# Half-Bridge.net
KiCad netlist of a schematic drawn in Altium Designer
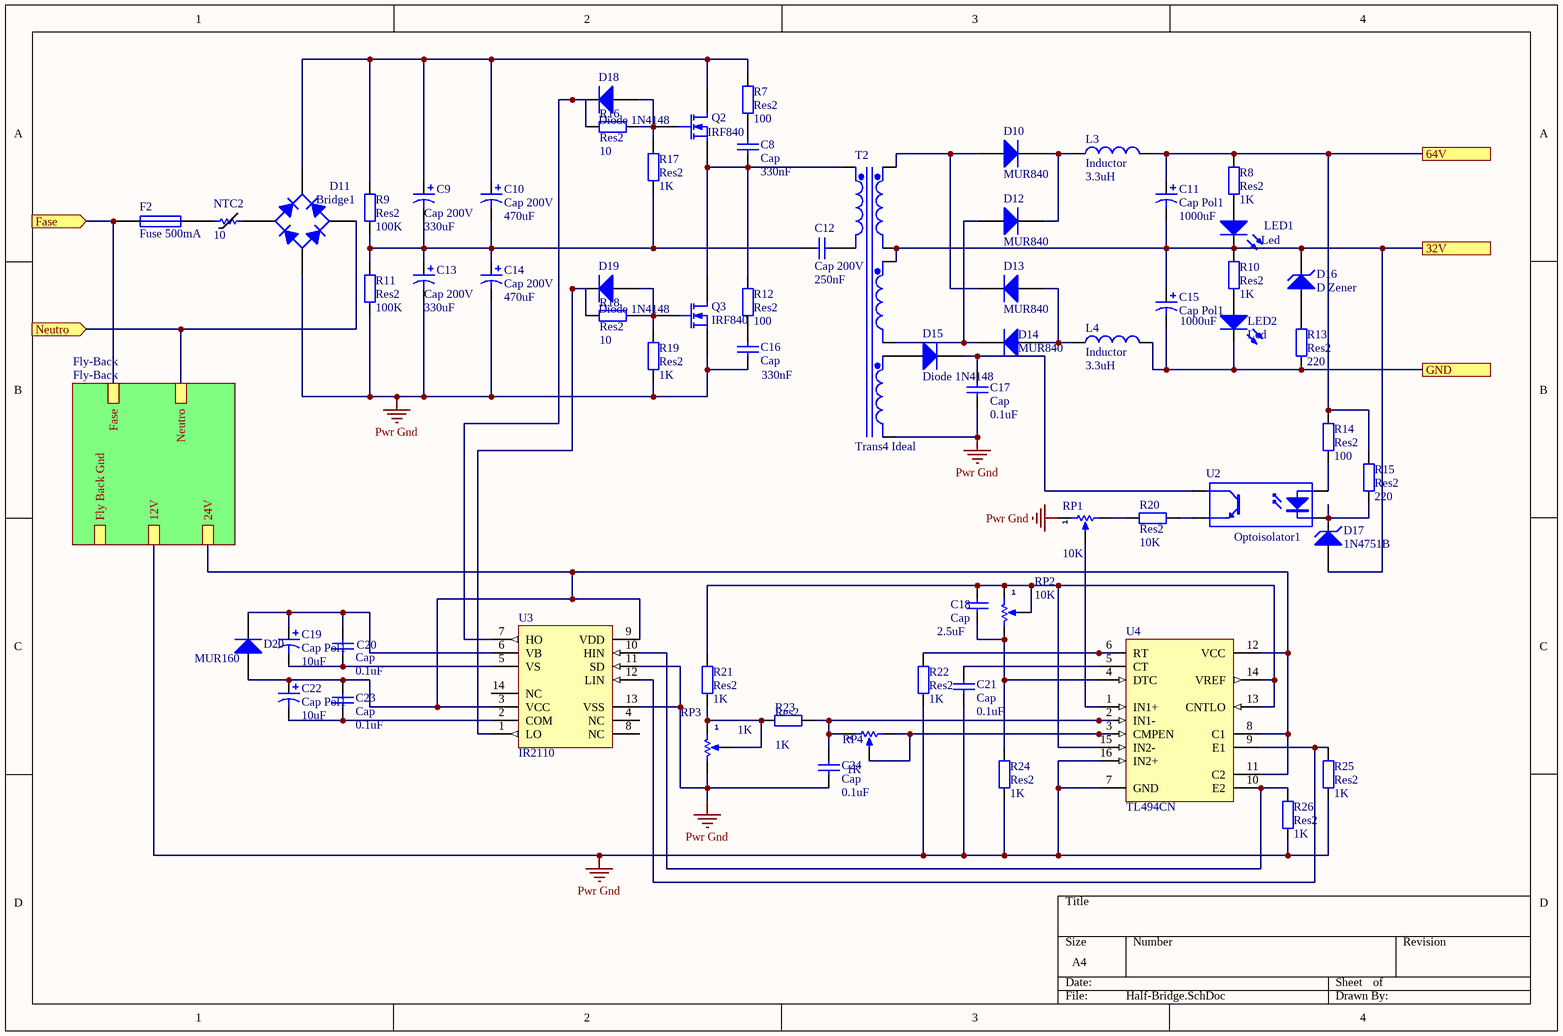
[diagram p0: Half-Bridge.SchDoc]

(export (version "E")
  (design (tool "Eeschema 10.0.6"))
  (components
    (comp (ref "C8")
      (value "Cap")
      (footprint "RAD-0.3")
      (description "Capacitor")
      (fields (field (name "ALTIUM_VALUE") "330nF") (field (name "PUBLISHER") "Altium Limited"))
      (libsource (lib "Miscellaneous Devices") (part "Cap"))
    )
    (comp (ref "C9")
      (value "Cap 200V")
      (footprint "RB7.6-15")
      (description "Polarized Capacitor (Radial)")
      (fields (field (name "ALTIUM_VALUE") "330uF") (field (name "PUBLISHER") "Altium Limited"))
      (libsource (lib "Miscellaneous Devices") (part "Cap Pol1"))
    )
    (comp (ref "C10")
      (value "Cap 200V")
      (footprint "RB7.6-15")
      (description "Polarized Capacitor (Radial)")
      (fields (field (name "ALTIUM_VALUE") "470uF") (field (name "PUBLISHER") "Altium Limited"))
      (libsource (lib "Miscellaneous Devices") (part "Cap Pol1"))
    )
    (comp (ref "C11")
      (value "Cap Pol1")
      (footprint "RB7.6-15")
      (description "Polarized Capacitor (Radial)")
      (fields (field (name "ALTIUM_VALUE") "1000uF") (field (name "PUBLISHER") "Altium Limited"))
      (libsource (lib "Miscellaneous Devices") (part "Cap Pol1"))
    )
    (comp (ref "C12")
      (value "Cap 200V")
      (footprint "RAD-0.3")
      (description "Capacitor")
      (fields (field (name "ALTIUM_VALUE") "250nF") (field (name "PUBLISHER") "Altium Limited"))
      (libsource (lib "Miscellaneous Devices") (part "Cap"))
    )
    (comp (ref "C13")
      (value "Cap 200V")
      (footprint "RB7.6-15")
      (description "Polarized Capacitor (Radial)")
      (fields (field (name "ALTIUM_VALUE") "330uF") (field (name "PUBLISHER") "Altium Limited"))
      (libsource (lib "Miscellaneous Devices") (part "Cap Pol1"))
    )
    (comp (ref "C14")
      (value "Cap 200V")
      (footprint "RB7.6-15")
      (description "Polarized Capacitor (Radial)")
      (fields (field (name "ALTIUM_VALUE") "470uF") (field (name "PUBLISHER") "Altium Limited"))
      (libsource (lib "Miscellaneous Devices") (part "Cap Pol1"))
    )
    (comp (ref "C15")
      (value "Cap Pol1")
      (footprint "RB7.6-15")
      (description "Polarized Capacitor (Radial)")
      (fields (field (name "ALTIUM_VALUE") "1000uF") (field (name "PUBLISHER") "Altium Limited"))
      (libsource (lib "Miscellaneous Devices") (part "Cap Pol1"))
    )
    (comp (ref "C16")
      (value "Cap")
      (footprint "RAD-0.3")
      (description "Capacitor")
      (fields (field (name "ALTIUM_VALUE") "330nF") (field (name "PUBLISHER") "Altium Limited"))
      (libsource (lib "Miscellaneous Devices") (part "Cap"))
    )
    (comp (ref "C17")
      (value "Cap")
      (footprint "RAD-0.3")
      (description "Capacitor")
      (fields (field (name "ALTIUM_VALUE") "0.1uF") (field (name "PUBLISHER") "Altium Limited"))
      (libsource (lib "Miscellaneous Devices") (part "Cap"))
    )
    (comp (ref "C18")
      (value "Cap")
      (footprint "RAD-0.3")
      (description "Capacitor")
      (fields (field (name "ALTIUM_VALUE") "2.5uF") (field (name "PUBLISHER") "Altium Limited"))
      (libsource (lib "Miscellaneous Devices") (part "Cap"))
    )
    (comp (ref "C19")
      (value "Cap Pol1")
      (footprint "RB7.6-15")
      (description "Polarized Capacitor (Radial)")
      (fields (field (name "ALTIUM_VALUE") "10uF") (field (name "PUBLISHER") "Altium Limited"))
      (libsource (lib "Miscellaneous Devices") (part "Cap Pol1"))
    )
    (comp (ref "C20")
      (value "Cap")
      (footprint "RAD-0.3")
      (description "Capacitor")
      (fields (field (name "ALTIUM_VALUE") "0.1uF") (field (name "PUBLISHER") "Altium Limited"))
      (libsource (lib "Miscellaneous Devices") (part "Cap"))
    )
    (comp (ref "C21")
      (value "Cap")
      (footprint "RAD-0.3")
      (description "Capacitor")
      (fields (field (name "ALTIUM_VALUE") "0.1uF") (field (name "PUBLISHER") "Altium Limited"))
      (libsource (lib "Miscellaneous Devices") (part "Cap"))
    )
    (comp (ref "C22")
      (value "Cap Pol1")
      (footprint "RB7.6-15")
      (description "Polarized Capacitor (Radial)")
      (fields (field (name "ALTIUM_VALUE") "10uF") (field (name "PUBLISHER") "Altium Limited"))
      (libsource (lib "Miscellaneous Devices") (part "Cap Pol1"))
    )
    (comp (ref "C23")
      (value "Cap")
      (footprint "RAD-0.3")
      (description "Capacitor")
      (fields (field (name "ALTIUM_VALUE") "0.1uF") (field (name "PUBLISHER") "Altium Limited"))
      (libsource (lib "Miscellaneous Devices") (part "Cap"))
    )
    (comp (ref "C24")
      (value "Cap")
      (footprint "RAD-0.3")
      (description "Capacitor")
      (fields (field (name "ALTIUM_VALUE") "0.1uF") (field (name "PUBLISHER") "Altium Limited"))
      (libsource (lib "Miscellaneous Devices") (part "Cap"))
    )
    (comp (ref "D10")
      (value "MUR840")
      (footprint "DO-35")
      (description "High Conductance Fast Diode")
      (fields (field (name "PUBLISHER") "Altium Limited"))
      (libsource (lib "Miscellaneous Devices") (part "Diode 1N4148"))
    )
    (comp (ref "D11")
      (value "Bridge1")
      (footprint "D-38")
      (description "Full Wave Diode Bridge")
      (fields (field (name "PUBLISHER") "Altium Limited"))
      (libsource (lib "Miscellaneous Devices") (part "Bridge1"))
    )
    (comp (ref "D12")
      (value "MUR840")
      (footprint "DO-35")
      (description "High Conductance Fast Diode")
      (fields (field (name "PUBLISHER") "Altium Limited"))
      (libsource (lib "Miscellaneous Devices") (part "Diode 1N4148"))
    )
    (comp (ref "D13")
      (value "MUR840")
      (footprint "DO-35")
      (description "High Conductance Fast Diode")
      (fields (field (name "PUBLISHER") "Altium Limited"))
      (libsource (lib "Miscellaneous Devices") (part "Diode 1N4148"))
    )
    (comp (ref "D14")
      (value "MUR840")
      (footprint "DO-35")
      (description "High Conductance Fast Diode")
      (fields (field (name "PUBLISHER") "Altium Limited"))
      (libsource (lib "Miscellaneous Devices") (part "Diode 1N4148"))
    )
    (comp (ref "D15")
      (value "Diode 1N4148")
      (footprint "DO-35")
      (description "High Conductance Fast Diode")
      (fields (field (name "PUBLISHER") "Altium Limited"))
      (libsource (lib "Miscellaneous Devices") (part "Diode 1N4148"))
    )
    (comp (ref "D16")
      (value "D Zener")
      (footprint "DIODE-0.7")
      (description "Zener Diode")
      (fields (field (name "PUBLISHER") "Altium Limited"))
      (libsource (lib "Miscellaneous Devices") (part "D Zener"))
    )
    (comp (ref "D17")
      (value "1N4751B")
      (footprint "DIODE-0.7")
      (description "Zener Diode")
      (fields (field (name "PUBLISHER") "Altium Limited"))
      (libsource (lib "Miscellaneous Devices") (part "D Zener"))
    )
    (comp (ref "D18")
      (value "Diode 1N4148")
      (footprint "DO-35")
      (description "High Conductance Fast Diode")
      (fields (field (name "PUBLISHER") "Altium Limited"))
      (libsource (lib "Miscellaneous Devices") (part "Diode 1N4148"))
    )
    (comp (ref "D19")
      (value "Diode 1N4148")
      (footprint "DO-35")
      (description "High Conductance Fast Diode")
      (fields (field (name "PUBLISHER") "Altium Limited"))
      (libsource (lib "Miscellaneous Devices") (part "Diode 1N4148"))
    )
    (comp (ref "D20")
      (value "MUR160")
      (footprint "DO-35")
      (description "High Conductance Fast Diode")
      (fields (field (name "PUBLISHER") "Altium Limited"))
      (libsource (lib "Miscellaneous Devices") (part "Diode 1N4148"))
    )
    (comp (ref "F2")
      (value "Fuse 500mA")
      (footprint "PIN-W2/E2.8")
      (description "Fuse")
      (fields (field (name "PUBLISHER") "Altium Limited"))
      (libsource (lib "Miscellaneous Devices") (part "Fuse 1"))
    )
    (comp (ref "L3")
      (value "Inductor")
      (footprint "0402-A")
      (fields (field (name "ALTIUM_VALUE") "3.3uH") (field (name "PUBLISHER") "Altium Limited"))
      (libsource (lib "Miscellaneous Devices") (part "Inductor"))
    )
    (comp (ref "L4")
      (value "Inductor")
      (footprint "0402-A")
      (fields (field (name "ALTIUM_VALUE") "3.3uH") (field (name "PUBLISHER") "Altium Limited"))
      (libsource (lib "Miscellaneous Devices") (part "Inductor"))
    )
    (comp (ref "LED1")
      (value "Diodo Led")
      (footprint "Led 3mm AMARILLO")
      (description "Led 3mm")
      (fields (field (name "VALOR") "Led"))
      (libsource (lib "RUF-Dispositivos-Grales") (part "Diodo Led"))
    )
    (comp (ref "LED2")
      (value "Diodo Led")
      (footprint "Led 3mm AMARILLO")
      (description "Led 3mm")
      (fields (field (name "VALOR") "Led"))
      (libsource (lib "RUF-Dispositivos-Grales") (part "Diodo Led"))
    )
    (comp (ref "NTC2")
      (value "Termistor NTC")
      (footprint "R0805")
      (description "Termistor NTC SMD")
      (fields (field (name "VALOR") "10"))
      (libsource (lib "RUF-Dispositivos-Grales") (part "Termistor NTC"))
    )
    (comp (ref "Q2")
      (value "IRF840")
      (footprint "E3")
      (description "N-Channel MOSFET")
      (fields (field (name "PUBLISHER") "Altium Limited"))
      (libsource (lib "Miscellaneous Devices") (part "MOSFET-N"))
    )
    (comp (ref "Q3")
      (value "IRF840")
      (footprint "E3")
      (description "N-Channel MOSFET")
      (fields (field (name "PUBLISHER") "Altium Limited"))
      (libsource (lib "Miscellaneous Devices") (part "MOSFET-N"))
    )
    (comp (ref "R7")
      (value "Res2")
      (footprint "AXIAL-0.4")
      (description "Resistor")
      (fields (field (name "ALTIUM_VALUE") "100") (field (name "PUBLISHER") "Altium Limited"))
      (libsource (lib "") (part "Res2_1"))
    )
    (comp (ref "R8")
      (value "Res2")
      (footprint "AXIAL-0.4")
      (description "Resistor")
      (fields (field (name "ALTIUM_VALUE") "1K") (field (name "PUBLISHER") "Altium Limited"))
      (libsource (lib "") (part "Res2_1"))
    )
    (comp (ref "R9")
      (value "Res2")
      (footprint "AXIAL-0.4")
      (description "Resistor")
      (fields (field (name "ALTIUM_VALUE") "100K") (field (name "PUBLISHER") "Altium Limited"))
      (libsource (lib "") (part "Res2_1"))
    )
    (comp (ref "R10")
      (value "Res2")
      (footprint "AXIAL-0.4")
      (description "Resistor")
      (fields (field (name "ALTIUM_VALUE") "1K") (field (name "PUBLISHER") "Altium Limited"))
      (libsource (lib "") (part "Res2_1"))
    )
    (comp (ref "R11")
      (value "Res2")
      (footprint "AXIAL-0.4")
      (description "Resistor")
      (fields (field (name "ALTIUM_VALUE") "100K") (field (name "PUBLISHER") "Altium Limited"))
      (libsource (lib "") (part "Res2_1"))
    )
    (comp (ref "R12")
      (value "Res2")
      (footprint "AXIAL-0.4")
      (description "Resistor")
      (fields (field (name "ALTIUM_VALUE") "100") (field (name "PUBLISHER") "Altium Limited"))
      (libsource (lib "") (part "Res2_1"))
    )
    (comp (ref "R13")
      (value "Res2")
      (footprint "AXIAL-0.4")
      (description "Resistor")
      (fields (field (name "ALTIUM_VALUE") "220") (field (name "PUBLISHER") "Altium Limited"))
      (libsource (lib "") (part "Res2_1"))
    )
    (comp (ref "R14")
      (value "Res2")
      (footprint "AXIAL-0.4")
      (description "Resistor")
      (fields (field (name "ALTIUM_VALUE") "100") (field (name "PUBLISHER") "Altium Limited"))
      (libsource (lib "") (part "Res2_1"))
    )
    (comp (ref "R15")
      (value "Res2")
      (footprint "AXIAL-0.4")
      (description "Resistor")
      (fields (field (name "ALTIUM_VALUE") "220") (field (name "PUBLISHER") "Altium Limited"))
      (libsource (lib "") (part "Res2_1"))
    )
    (comp (ref "R16")
      (value "Res2")
      (footprint "AXIAL-0.4")
      (description "Resistor")
      (fields (field (name "ALTIUM_VALUE") "10") (field (name "PUBLISHER") "Altium Limited"))
      (libsource (lib "") (part "Res2_3"))
    )
    (comp (ref "R17")
      (value "Res2")
      (footprint "AXIAL-0.4")
      (description "Resistor")
      (fields (field (name "ALTIUM_VALUE") "1K") (field (name "PUBLISHER") "Altium Limited"))
      (libsource (lib "") (part "Res2_1"))
    )
    (comp (ref "R18")
      (value "Res2")
      (footprint "AXIAL-0.4")
      (description "Resistor")
      (fields (field (name "ALTIUM_VALUE") "10") (field (name "PUBLISHER") "Altium Limited"))
      (libsource (lib "") (part "Res2_2"))
    )
    (comp (ref "R19")
      (value "Res2")
      (footprint "AXIAL-0.4")
      (description "Resistor")
      (fields (field (name "ALTIUM_VALUE") "1K") (field (name "PUBLISHER") "Altium Limited"))
      (libsource (lib "Miscellaneous Devices") (part "Res2"))
    )
    (comp (ref "R20")
      (value "Res2")
      (footprint "AXIAL-0.4")
      (description "Resistor")
      (fields (field (name "ALTIUM_VALUE") "10K") (field (name "PUBLISHER") "Altium Limited"))
      (libsource (lib "") (part "Res2_2"))
    )
    (comp (ref "R21")
      (value "Res2")
      (footprint "AXIAL-0.4")
      (description "Resistor")
      (fields (field (name "ALTIUM_VALUE") "1K") (field (name "PUBLISHER") "Altium Limited"))
      (libsource (lib "") (part "Res2_1"))
    )
    (comp (ref "R22")
      (value "Res2")
      (footprint "AXIAL-0.4")
      (description "Resistor")
      (fields (field (name "ALTIUM_VALUE") "1K") (field (name "PUBLISHER") "Altium Limited"))
      (libsource (lib "") (part "Res2_1"))
    )
    (comp (ref "R23")
      (value "Res2")
      (footprint "AXIAL-0.4")
      (description "Resistor")
      (fields (field (name "ALTIUM_VALUE") "1K") (field (name "PUBLISHER") "Altium Limited"))
      (libsource (lib "") (part "Res2_3"))
    )
    (comp (ref "R24")
      (value "Res2")
      (footprint "AXIAL-0.4")
      (description "Resistor")
      (fields (field (name "ALTIUM_VALUE") "1K") (field (name "PUBLISHER") "Altium Limited"))
      (libsource (lib "") (part "Res2_1"))
    )
    (comp (ref "R25")
      (value "Res2")
      (footprint "AXIAL-0.4")
      (description "Resistor")
      (fields (field (name "ALTIUM_VALUE") "1K") (field (name "PUBLISHER") "Altium Limited"))
      (libsource (lib "") (part "Res2_1"))
    )
    (comp (ref "R26")
      (value "Res2")
      (footprint "AXIAL-0.4")
      (description "Resistor")
      (fields (field (name "ALTIUM_VALUE") "1K") (field (name "PUBLISHER") "Altium Limited"))
      (libsource (lib "") (part "Res2_1"))
    )
    (comp (ref "RP1")
      (value "Trimpot")
      (footprint "Trimpot Multivuelta Horizontal")
      (description "Preset")
      (fields (field (name "VALOR") "10K"))
      (libsource (lib "RUF-Dispositivos-Grales") (part "Trimpot"))
    )
    (comp (ref "RP2")
      (value "Trimpot")
      (footprint "Trimpot Multivuelta Horizontal")
      (description "Preset")
      (fields (field (name "VALOR") "10K"))
      (libsource (lib "RUF-Dispositivos-Grales") (part "Trimpot"))
    )
    (comp (ref "RP3")
      (value "Trimpot")
      (footprint "Trimpot Multivuelta Horizontal")
      (description "Preset")
      (fields (field (name "VALOR") "1K"))
      (libsource (lib "RUF-Dispositivos-Grales") (part "Trimpot"))
    )
    (comp (ref "RP4")
      (value "Trimpot")
      (footprint "Trimpot Multivuelta Horizontal")
      (description "Preset")
      (fields (field (name "VALOR") "1K"))
      (libsource (lib "RUF-Dispositivos-Grales") (part "Trimpot"))
    )
    (comp (ref "T2")
      (value "Trans4 Ideal")
      (footprint "TRF_8")
      (description "Four-winding Transformer (Ideal)")
      (fields (field (name "PUBLISHER") "Altium Limited"))
      (libsource (lib "Miscellaneous Devices") (part "Trans4 Ideal"))
    )
    (comp (ref "U2")
      (value "Optoisolator1")
      (footprint "DIP-4")
      (description "4-Pin Phototransistor Optocoupler")
      (fields (field (name "PUBLISHER") "Altium Limited"))
      (libsource (lib "Miscellaneous Devices") (part "Optoisolator1"))
    )
    (comp (ref "U3")
      (value "IR2110")
      (footprint "PDIP14")
      (description "High and Low Side Driver")
      (fields (field (name "PUBLISHER") "Altium Limited"))
      (libsource (lib "IR Interface Bridge Driver") (part "IR2110"))
    )
    (comp (ref "U4")
      (value "TL494CN")
      (footprint "DIP-16")
      (description "Switchmode Pulse Width Modulation Control Circuit")
      (fields (field (name "PUBLISHER") "Altium Limited"))
      (libsource (lib "ON Semi Power Mgt SMPS Controller") (part "TL494CN"))
    )
  )
  (nets
    (net (code "1") (name "/24V") (class "Default")
      (node (ref "C22") (pin "1") (pinfunction "1_1") (pintype "passive"))
      (node (ref "C23") (pin "2") (pinfunction "2_2") (pintype "passive"))
      (node (ref "D20") (pin "1") (pinfunction "A_1") (pintype "passive"))
      (node (ref "U3") (pin "3") (pinfunction "VCC_3") (pintype "power_in"))
      (node (ref "U3") (pin "9") (pinfunction "VDD_9") (pintype "power_in"))
      (node (ref "U4") (pin "11") (pinfunction "C2_11") (pintype "passive"))
      (node (ref "U4") (pin "12") (pinfunction "VCC_12") (pintype "power_in"))
      (node (ref "U4") (pin "8") (pinfunction "C1_8") (pintype "passive"))
    )
    (net (code "2") (name "/32V") (class "Default")
      (node (ref "C11") (pin "2") (pinfunction "2_2") (pintype "passive"))
      (node (ref "C15") (pin "1") (pinfunction "1_1") (pintype "passive"))
      (node (ref "D16") (pin "2") (pinfunction "K_2") (pintype "passive"))
      (node (ref "D17") (pin "1") (pinfunction "A_1") (pintype "passive"))
      (node (ref "LED1") (pin "2") (pinfunction "K_2") (pintype "passive"))
      (node (ref "R10") (pin "2") (pinfunction "2_2") (pintype "passive"))
      (node (ref "T2") (pin "4") (pinfunction "Sec1-_4") (pintype "passive"))
      (node (ref "T2") (pin "5") (pinfunction "Sec2+_5") (pintype "passive"))
    )
    (net (code "3") (name "/64V") (class "Default")
      (node (ref "C11") (pin "1") (pinfunction "1_1") (pintype "passive"))
      (node (ref "L3") (pin "2") (pinfunction "2_2") (pintype "passive"))
      (node (ref "R14") (pin "2") (pinfunction "2_2") (pintype "passive"))
      (node (ref "R15") (pin "2") (pinfunction "2_2") (pintype "passive"))
      (node (ref "R8") (pin "2") (pinfunction "2_2") (pintype "passive"))
    )
    (net (code "4") (name "/Fase") (class "Default")
      (node (ref "F2") (pin "1") (pinfunction "1_1") (pintype "passive"))
    )
    (net (code "6") (name "/GND") (class "Default")
      (node (ref "C15") (pin "2") (pinfunction "2_2") (pintype "passive"))
      (node (ref "L4") (pin "2") (pinfunction "2_2") (pintype "passive"))
      (node (ref "LED2") (pin "2") (pinfunction "K_2") (pintype "passive"))
      (node (ref "R13") (pin "1") (pinfunction "1_1") (pintype "passive"))
    )
    (net (code "7") (name "/Neutro") (class "Default")
      (node (ref "D11") (pin "2") (pinfunction "C_2") (pintype "passive"))
    )
    (net (code "8") (name "Net-(C8-Pad2)") (class "Default")
      (node (ref "C8") (pin "2") (pinfunction "2_2") (pintype "passive"))
      (node (ref "R7") (pin "1") (pinfunction "1_1") (pintype "passive"))
    )
    (net (code "9") (name "Net-(C10-Pad2)") (class "Default")
      (node (ref "C10") (pin "2") (pinfunction "2_2") (pintype "passive"))
      (node (ref "C12") (pin "1") (pinfunction "1_1") (pintype "passive"))
      (node (ref "C13") (pin "1") (pinfunction "1_1") (pintype "passive"))
      (node (ref "C14") (pin "1") (pinfunction "1_1") (pintype "passive"))
      (node (ref "C9") (pin "2") (pinfunction "2_2") (pintype "passive"))
      (node (ref "R11") (pin "2") (pinfunction "2_2") (pintype "passive"))
      (node (ref "R17") (pin "1") (pinfunction "1_1") (pintype "passive"))
      (node (ref "R9") (pin "1") (pinfunction "1_1") (pintype "passive"))
    )
    (net (code "10") (name "Net-(C16-Pad2)") (class "Default")
      (node (ref "C16") (pin "2") (pinfunction "2_2") (pintype "passive"))
      (node (ref "R12") (pin "1") (pinfunction "1_1") (pintype "passive"))
    )
    (net (code "11") (name "Net-(D10-A)") (class "Default")
      (node (ref "D10") (pin "1") (pinfunction "A_1") (pintype "passive"))
      (node (ref "D13") (pin "2") (pinfunction "K_2") (pintype "passive"))
      (node (ref "T2") (pin "3") (pinfunction "Sec1+_3") (pintype "passive"))
    )
    (net (code "12") (name "Net-(D10-K)") (class "Default")
      (node (ref "D10") (pin "2") (pinfunction "K_2") (pintype "passive"))
      (node (ref "D12") (pin "2") (pinfunction "K_2") (pintype "passive"))
      (node (ref "L3") (pin "1") (pinfunction "1_1") (pintype "passive"))
    )
    (net (code "13") (name "Net-(D11-C-Pad4)") (class "Default")
      (node (ref "D11") (pin "4") (pinfunction "C_4") (pintype "passive"))
      (node (ref "NTC2") (pin "1") (pinfunction "1_1") (pintype "passive"))
    )
    (net (code "14") (name "Net-(D11-K)") (class "Default")
      (node (ref "C10") (pin "1") (pinfunction "1_1") (pintype "passive"))
      (node (ref "C9") (pin "1") (pinfunction "1_1") (pintype "passive"))
      (node (ref "D11") (pin "1") (pinfunction "K_1") (pintype "passive"))
      (node (ref "Q2") (pin "1") (pinfunction "D_1") (pintype "passive"))
      (node (ref "R7") (pin "2") (pinfunction "2_2") (pintype "passive"))
      (node (ref "R9") (pin "2") (pinfunction "2_2") (pintype "passive"))
    )
    (net (code "15") (name "Net-(D12-A)") (class "Default")
      (node (ref "D12") (pin "1") (pinfunction "A_1") (pintype "passive"))
      (node (ref "D14") (pin "2") (pinfunction "K_2") (pintype "passive"))
      (node (ref "T2") (pin "6") (pinfunction "Sec2-_6") (pintype "passive"))
    )
    (net (code "16") (name "Net-(D13-A)") (class "Default")
      (node (ref "D13") (pin "1") (pinfunction "A_1") (pintype "passive"))
      (node (ref "D14") (pin "1") (pinfunction "A_1") (pintype "passive"))
      (node (ref "L4") (pin "1") (pinfunction "1_1") (pintype "passive"))
    )
    (net (code "17") (name "Net-(D15-A)") (class "Default")
      (node (ref "D15") (pin "1") (pinfunction "A_1") (pintype "passive"))
      (node (ref "T2") (pin "7") (pinfunction "Sec3+_7") (pintype "passive"))
    )
    (net (code "18") (name "Net-(D15-K)") (class "Default")
      (node (ref "C17") (pin "2") (pinfunction "2_2") (pintype "passive"))
      (node (ref "D15") (pin "2") (pinfunction "K_2") (pintype "passive"))
      (node (ref "U2") (pin "4") (pinfunction "C_4") (pintype "passive"))
    )
    (net (code "19") (name "Net-(D16-A)") (class "Default")
      (node (ref "D16") (pin "1") (pinfunction "A_1") (pintype "passive"))
      (node (ref "R13") (pin "2") (pinfunction "2_2") (pintype "passive"))
    )
    (net (code "20") (name "Net-(D17-K)") (class "Default")
      (node (ref "D17") (pin "2") (pinfunction "K_2") (pintype "passive"))
      (node (ref "R15") (pin "1") (pinfunction "1_1") (pintype "passive"))
      (node (ref "U2") (pin "2") (pinfunction "K_2") (pintype "passive"))
    )
    (net (code "21") (name "Net-(D18-A)") (class "Default")
      (node (ref "D18") (pin "1") (pinfunction "A_1") (pintype "passive"))
      (node (ref "Q2") (pin "2") (pinfunction "G_2") (pintype "passive"))
      (node (ref "R16") (pin "2") (pinfunction "2_2") (pintype "passive"))
      (node (ref "R17") (pin "2") (pinfunction "2_2") (pintype "passive"))
    )
    (net (code "22") (name "Net-(D18-K)") (class "Default")
      (node (ref "D18") (pin "2") (pinfunction "K_2") (pintype "passive"))
      (node (ref "R16") (pin "1") (pinfunction "1_1") (pintype "passive"))
      (node (ref "U3") (pin "7") (pinfunction "HO_7") (pintype "output"))
    )
    (net (code "23") (name "Net-(D19-A)") (class "Default")
      (node (ref "D19") (pin "1") (pinfunction "A_1") (pintype "passive"))
      (node (ref "Q3") (pin "2") (pinfunction "G_2") (pintype "passive"))
      (node (ref "R18") (pin "1") (pinfunction "1_1") (pintype "passive"))
      (node (ref "R19") (pin "1") (pinfunction "1_1") (pintype "passive"))
    )
    (net (code "24") (name "Net-(D19-K)") (class "Default")
      (node (ref "D19") (pin "2") (pinfunction "K_2") (pintype "passive"))
      (node (ref "R18") (pin "2") (pinfunction "2_2") (pintype "passive"))
      (node (ref "U3") (pin "1") (pinfunction "LO_1") (pintype "output"))
    )
    (net (code "25") (name "Net-(D20-K)") (class "Default")
      (node (ref "C19") (pin "1") (pinfunction "1_1") (pintype "passive"))
      (node (ref "C20") (pin "2") (pinfunction "2_2") (pintype "passive"))
      (node (ref "D20") (pin "2") (pinfunction "K_2") (pintype "passive"))
      (node (ref "U3") (pin "6") (pinfunction "VB_6") (pintype "power_in"))
    )
    (net (code "26") (name "Net-(F2-Pad2)") (class "Default")
      (node (ref "F2") (pin "2") (pinfunction "2_2") (pintype "passive"))
      (node (ref "NTC2") (pin "2") (pinfunction "2_2") (pintype "passive"))
    )
    (net (code "27") (name "Net-(LED1-A)") (class "Default")
      (node (ref "LED1") (pin "1") (pinfunction "A_1") (pintype "passive"))
      (node (ref "R8") (pin "1") (pinfunction "1_1") (pintype "passive"))
    )
    (net (code "28") (name "Net-(LED2-A)") (class "Default")
      (node (ref "LED2") (pin "1") (pinfunction "A_1") (pintype "passive"))
      (node (ref "R10") (pin "1") (pinfunction "1_1") (pintype "passive"))
    )
    (net (code "29") (name "Net-(Q2-S)") (class "Default")
      (node (ref "C8") (pin "1") (pinfunction "1_1") (pintype "passive"))
      (node (ref "Q2") (pin "3") (pinfunction "S_3") (pintype "passive"))
      (node (ref "Q3") (pin "1") (pinfunction "D_1") (pintype "passive"))
      (node (ref "R12") (pin "2") (pinfunction "2_2") (pintype "passive"))
      (node (ref "T2") (pin "1") (pinfunction "Pri+_1") (pintype "passive"))
    )
    (net (code "30") (name "Net-(RP1-BOT)") (class "Default")
      (node (ref "R20") (pin "2") (pinfunction "2_2") (pintype "passive"))
      (node (ref "RP1") (pin "2") (pinfunction "BOT_2") (pintype "passive"))
    )
    (net (code "31") (name "Net-(RP1-TAP)") (class "Default")
      (node (ref "RP1") (pin "3") (pinfunction "TAP_3") (pintype "passive"))
      (node (ref "U4") (pin "1") (pinfunction "IN1+_1") (pintype "input"))
    )
    (net (code "32") (name "Net-(RP2-BOT)") (class "Default")
      (node (ref "C18") (pin "1") (pinfunction "1_1") (pintype "passive"))
      (node (ref "R24") (pin "2") (pinfunction "2_2") (pintype "passive"))
      (node (ref "RP2") (pin "2") (pinfunction "BOT_2") (pintype "passive"))
      (node (ref "U4") (pin "4") (pinfunction "DTC_4") (pintype "input"))
    )
    (net (code "33") (name "Net-(RP2-TAP)") (class "Default")
      (node (ref "C18") (pin "2") (pinfunction "2_2") (pintype "passive"))
      (node (ref "R21") (pin "2") (pinfunction "2_2") (pintype "passive"))
      (node (ref "RP2") (pin "1") (pinfunction "TOP_1") (pintype "passive"))
      (node (ref "RP2") (pin "3") (pinfunction "TAP_3") (pintype "passive"))
      (node (ref "U4") (pin "13") (pinfunction "CNTLO_13") (pintype "input"))
      (node (ref "U4") (pin "14") (pinfunction "VREF_14") (pintype "output"))
      (node (ref "U4") (pin "15") (pinfunction "IN2-_15") (pintype "input"))
    )
    (net (code "34") (name "Net-(RP3-TAP)") (class "Default")
      (node (ref "R21") (pin "1") (pinfunction "1_1") (pintype "passive"))
      (node (ref "R23") (pin "1") (pinfunction "1_1") (pintype "passive"))
      (node (ref "RP3") (pin "1") (pinfunction "TOP_1") (pintype "passive"))
      (node (ref "RP3") (pin "3") (pinfunction "TAP_3") (pintype "passive"))
    )
    (net (code "35") (name "Net-(RP4-BOT)") (class "Default")
      (node (ref "RP4") (pin "2") (pinfunction "BOT_2") (pintype "passive"))
      (node (ref "RP4") (pin "3") (pinfunction "TAP_3") (pintype "passive"))
      (node (ref "U4") (pin "3") (pinfunction "CMPEN_3") (pintype "input"))
    )
    (net (code "36") (name "Net-(RP4-TOP)") (class "Default")
      (node (ref "C24") (pin "2") (pinfunction "2_2") (pintype "passive"))
      (node (ref "R23") (pin "2") (pinfunction "2_2") (pintype "passive"))
      (node (ref "RP4") (pin "1") (pinfunction "TOP_1") (pintype "passive"))
      (node (ref "U4") (pin "2") (pinfunction "IN1-_2") (pintype "input"))
    )
    (net (code "37") (name "Net-(T2-Pri-)") (class "Default")
      (node (ref "C12") (pin "2") (pinfunction "2_2") (pintype "passive"))
      (node (ref "T2") (pin "2") (pinfunction "Pri-_2") (pintype "passive"))
    )
    (net (code "38") (name "Net-(U2-A)") (class "Default")
      (node (ref "R14") (pin "1") (pinfunction "1_1") (pintype "passive"))
      (node (ref "U2") (pin "1") (pinfunction "A_1") (pintype "passive"))
    )
    (net (code "39") (name "Net-(U2-E)") (class "Default")
      (node (ref "R20") (pin "1") (pinfunction "1_1") (pintype "passive"))
      (node (ref "U2") (pin "3") (pinfunction "E_3") (pintype "passive"))
    )
    (net (code "40") (name "Net-(U3-COM)") (class "Default")
      (node (ref "C22") (pin "2") (pinfunction "2_2") (pintype "passive"))
      (node (ref "C23") (pin "1") (pinfunction "1_1") (pintype "passive"))
      (node (ref "U3") (pin "2") (pinfunction "COM_2") (pintype "power_in"))
    )
    (net (code "41") (name "Net-(U3-HIN)") (class "Default")
      (node (ref "R26") (pin "2") (pinfunction "2_2") (pintype "passive"))
      (node (ref "U3") (pin "10") (pinfunction "HIN_10") (pintype "input"))
      (node (ref "U4") (pin "10") (pinfunction "E2_10") (pintype "passive"))
    )
    (net (code "42") (name "Net-(U3-LIN)") (class "Default")
      (node (ref "R25") (pin "2") (pinfunction "2_2") (pintype "passive"))
      (node (ref "U3") (pin "12") (pinfunction "LIN_12") (pintype "input"))
      (node (ref "U4") (pin "9") (pinfunction "E1_9") (pintype "passive"))
    )
    (net (code "43") (name "Net-(U3-VS)") (class "Default")
      (node (ref "C19") (pin "2") (pinfunction "2_2") (pintype "passive"))
      (node (ref "C20") (pin "1") (pinfunction "1_1") (pintype "passive"))
      (node (ref "U3") (pin "5") (pinfunction "VS_5") (pintype "power_in"))
    )
    (net (code "44") (name "Net-(U4-CT)") (class "Default")
      (node (ref "C21") (pin "2") (pinfunction "2_2") (pintype "passive"))
      (node (ref "U4") (pin "5") (pinfunction "CT_5") (pintype "passive"))
    )
    (net (code "45") (name "Net-(U4-RT)") (class "Default")
      (node (ref "R22") (pin "2") (pinfunction "2_2") (pintype "passive"))
      (node (ref "U4") (pin "6") (pinfunction "RT_6") (pintype "passive"))
    )
    (net (code "46") (name "Pwr Gnd") (class "Default")
      (node (ref "C13") (pin "2") (pinfunction "2_2") (pintype "passive"))
      (node (ref "C14") (pin "2") (pinfunction "2_2") (pintype "passive"))
      (node (ref "C16") (pin "1") (pinfunction "1_1") (pintype "passive"))
      (node (ref "C17") (pin "1") (pinfunction "1_1") (pintype "passive"))
      (node (ref "C21") (pin "1") (pinfunction "1_1") (pintype "passive"))
      (node (ref "C24") (pin "1") (pinfunction "1_1") (pintype "passive"))
      (node (ref "D11") (pin "3") (pinfunction "A_3") (pintype "passive"))
      (node (ref "Q3") (pin "3") (pinfunction "S_3") (pintype "passive"))
      (node (ref "R11") (pin "1") (pinfunction "1_1") (pintype "passive"))
      (node (ref "R19") (pin "2") (pinfunction "2_2") (pintype "passive"))
      (node (ref "R22") (pin "1") (pinfunction "1_1") (pintype "passive"))
      (node (ref "R24") (pin "1") (pinfunction "1_1") (pintype "passive"))
      (node (ref "R25") (pin "1") (pinfunction "1_1") (pintype "passive"))
      (node (ref "R26") (pin "1") (pinfunction "1_1") (pintype "passive"))
      (node (ref "RP1") (pin "1") (pinfunction "TOP_1") (pintype "passive"))
      (node (ref "RP3") (pin "2") (pinfunction "BOT_2") (pintype "passive"))
      (node (ref "T2") (pin "8") (pinfunction "Sec3-_8") (pintype "passive"))
      (node (ref "U3") (pin "11") (pinfunction "SD_11") (pintype "input"))
      (node (ref "U3") (pin "13") (pinfunction "VSS_13") (pintype "power_in"))
      (node (ref "U4") (pin "16") (pinfunction "IN2+_16") (pintype "input"))
      (node (ref "U4") (pin "7") (pinfunction "GND_7") (pintype "power_in"))
    )
    (net (code "47") (name "unconnected-(U3-NC-Pad4)") (class "Default")
      (node (ref "U3") (pin "4") (pinfunction "NC_4") (pintype "passive"))
    )
    (net (code "48") (name "unconnected-(U3-NC-Pad8)") (class "Default")
      (node (ref "U3") (pin "8") (pinfunction "NC_8") (pintype "passive"))
    )
    (net (code "49") (name "unconnected-(U3-NC-Pad14)") (class "Default")
      (node (ref "U3") (pin "14") (pinfunction "NC_14") (pintype "passive"))
    )
  )
)
